# CP2102_USB_to_Serial_Breakout_v12.net
KiCad netlist of a schematic drawn in EAGLE
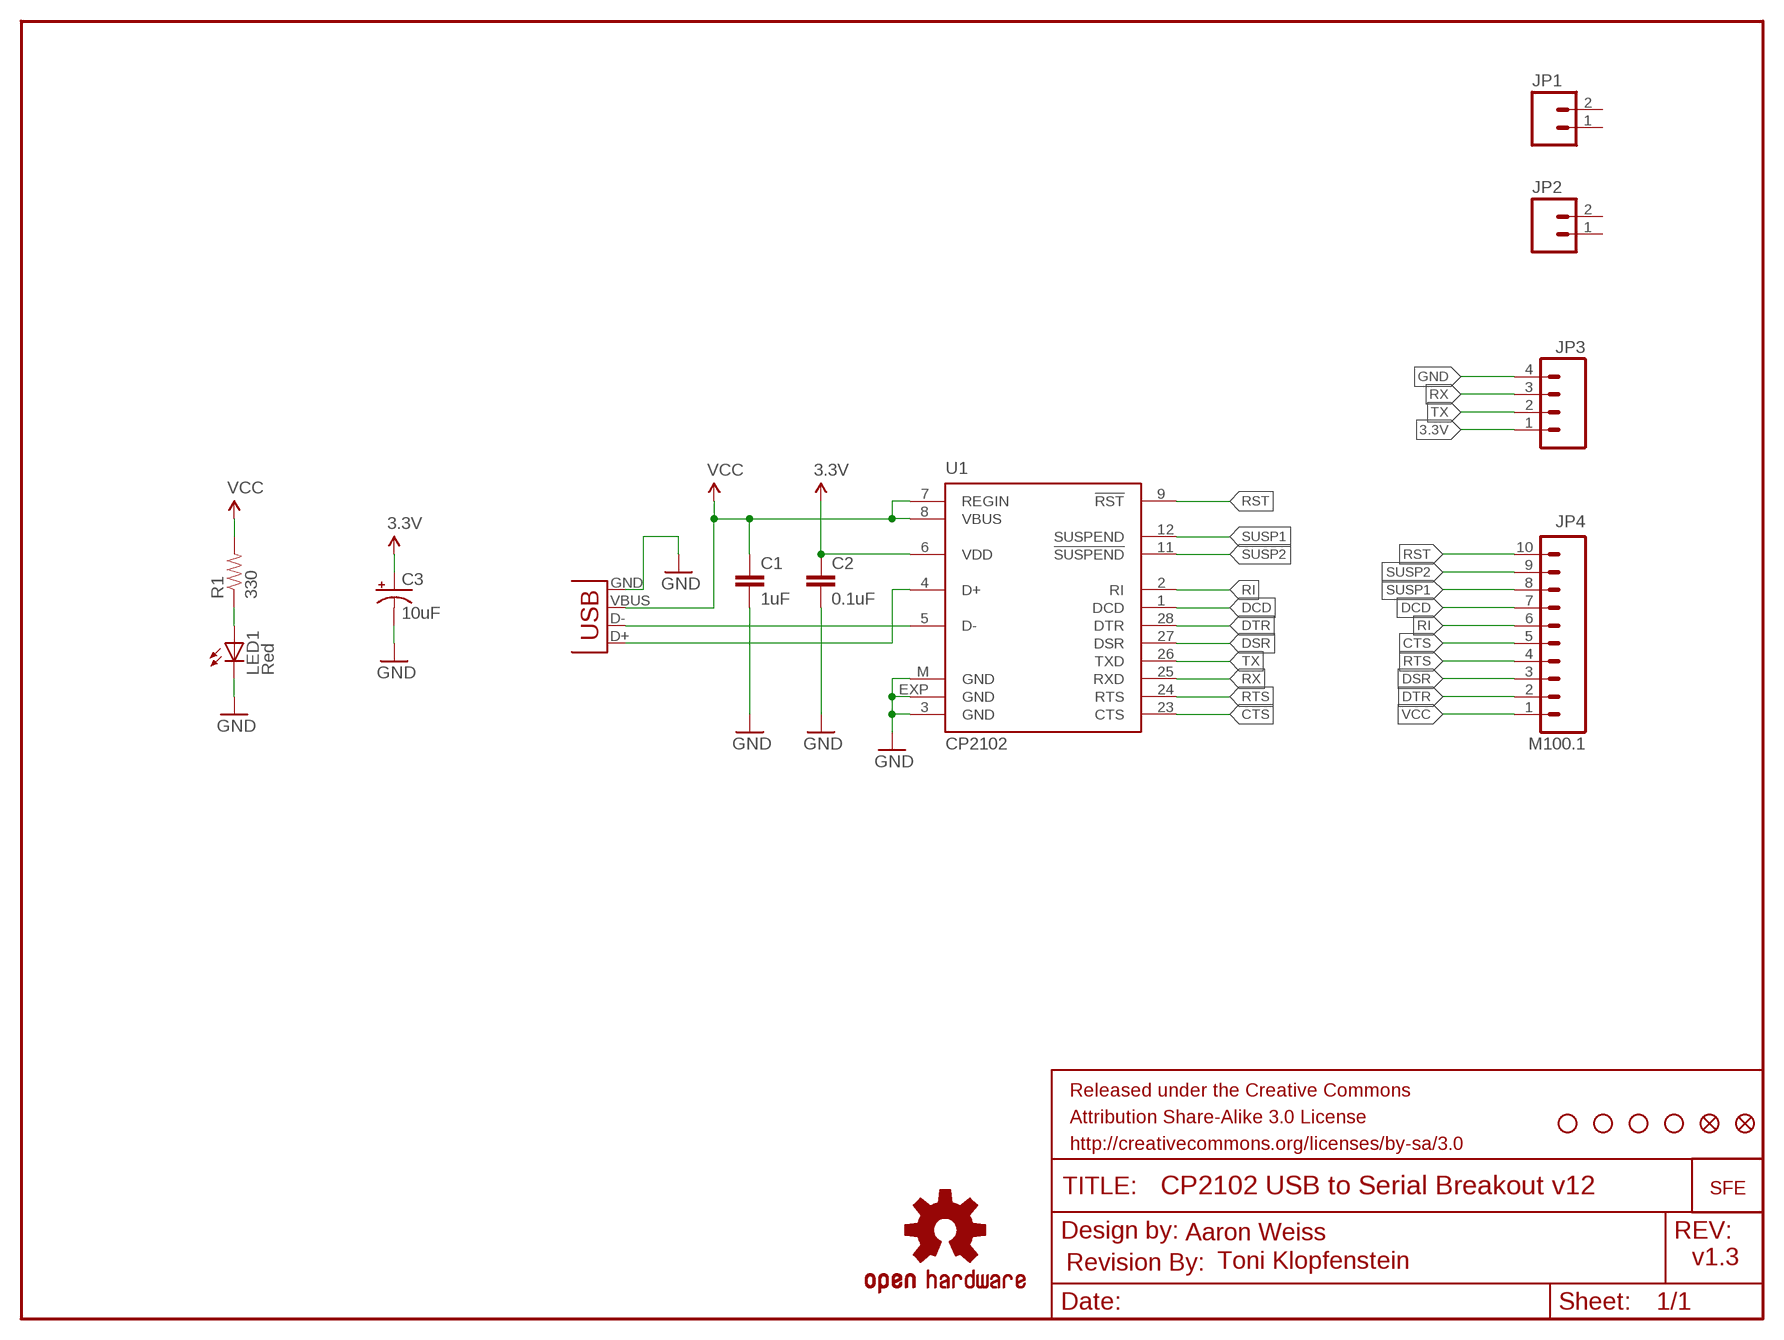
[diagram p0: schematic, sheet 1]

(export (version "E")
  (design (tool "Eeschema 10.0.6"))
  (components
    (comp (ref "C1")
      (value "1uF")
      (footprint "eagle-import:0603-CAP")
      (libsource (lib "eagle-import") (part "1.0UF-16V-10%(0603)"))
    )
    (comp (ref "C2")
      (value "0.1uF")
      (footprint "eagle-import:0603-CAP")
      (libsource (lib "eagle-import") (part "0.1UF-25V(+80/-20%)(0603)"))
    )
    (comp (ref "C3")
      (value "10uF")
      (footprint "eagle-import:EIA3216")
      (libsource (lib "eagle-import") (part "CAP_POL1206"))
    )
    (comp (ref "FRAME1")
      (value "FRAME-LETTER")
      (footprint "eagle-import:CREATIVE_COMMONS")
      (libsource (lib "eagle-import") (part "FRAME-LETTER"))
    )
    (comp (ref "JP1")
      (value "M02PTH")
      (footprint "eagle-import:1X02")
      (libsource (lib "eagle-import") (part "M02PTH"))
    )
    (comp (ref "JP2")
      (value "M02PTH")
      (footprint "eagle-import:1X02")
      (libsource (lib "eagle-import") (part "M02PTH"))
    )
    (comp (ref "JP3")
      (value "M04PTH")
      (footprint "eagle-import:1X04")
      (libsource (lib "eagle-import") (part "M04PTH"))
    )
    (comp (ref "JP4")
      (value "M100.1")
      (footprint "eagle-import:1X10")
      (libsource (lib "eagle-import") (part "M100.1"))
    )
    (comp (ref "LED1")
      (value "Red")
      (footprint "eagle-import:LED-1206")
      (libsource (lib "eagle-import") (part "LED1206"))
    )
    (comp (ref "LOGO1")
      (value "OSHW-LOGOS")
      (footprint "eagle-import:OSHW-LOGO-S")
      (libsource (lib "eagle-import") (part "OSHW-LOGOS"))
    )
    (comp (ref "R1")
      (value "330")
      (footprint "eagle-import:0603-RES")
      (libsource (lib "eagle-import") (part "330OHM1/10W1%(0603)"))
    )
    (comp (ref "U$1")
      (value "LOGO-SFENEW")
      (footprint "eagle-import:SFE-NEW-WEBLOGO")
      (libsource (lib "eagle-import") (part "LOGO-SFENEW"))
    )
    (comp (ref "U$2")
      (value "FIDUCIAL1X2")
      (footprint "eagle-import:FIDUCIAL-1X2")
      (libsource (lib "eagle-import") (part "FIDUCIAL1X2"))
    )
    (comp (ref "U$3")
      (value "FIDUCIAL1X2")
      (footprint "eagle-import:FIDUCIAL-1X2")
      (libsource (lib "eagle-import") (part "FIDUCIAL1X2"))
    )
    (comp (ref "U$4")
      (value "REVISION")
      (footprint "eagle-import:REVISION")
      (libsource (lib "eagle-import") (part "REVISION"))
    )
    (comp (ref "U$6")
      (value "STAND-OFF")
      (footprint "eagle-import:STAND-OFF")
      (libsource (lib "eagle-import") (part "STAND-OFF"))
    )
    (comp (ref "U$7")
      (value "STAND-OFF")
      (footprint "eagle-import:STAND-OFF")
      (libsource (lib "eagle-import") (part "STAND-OFF"))
    )
    (comp (ref "U$8")
      (value "STAND-OFF")
      (footprint "eagle-import:STAND-OFF")
      (libsource (lib "eagle-import") (part "STAND-OFF"))
    )
    (comp (ref "U$9")
      (value "STAND-OFF")
      (footprint "eagle-import:STAND-OFF")
      (libsource (lib "eagle-import") (part "STAND-OFF"))
    )
    (comp (ref "U1")
      (value "CP2102")
      (footprint "eagle-import:MLP28")
      (libsource (lib "eagle-import") (part "CP210X_USB_UART"))
    )
    (comp (ref "X1")
      (value "USBPTH")
      (footprint "eagle-import:USB-B-PTH")
      (libsource (lib "eagle-import") (part "USBPTH"))
    )
  )
  (nets
    (net (code "1") (name "3.3V") (class "Default")
      (node (ref "C2") (pin "1") (pinfunction "1_1") (pintype "passive"))
      (node (ref "C3") (pin "A") (pinfunction "+_A") (pintype "passive"))
      (node (ref "JP3") (pin "1") (pinfunction "1_1") (pintype "passive"))
      (node (ref "U1") (pin "6") (pinfunction "VDD_6") (pintype "power_in"))
    )
    (net (code "2") (name "CTS") (class "Default")
      (node (ref "JP4") (pin "5") (pinfunction "5_5") (pintype "passive"))
      (node (ref "U1") (pin "23") (pinfunction "CTS_23") (pintype "input"))
    )
    (net (code "3") (name "DCD") (class "Default")
      (node (ref "JP4") (pin "7") (pinfunction "7_7") (pintype "passive"))
      (node (ref "U1") (pin "1") (pinfunction "DCD_1") (pintype "input"))
    )
    (net (code "4") (name "DSR") (class "Default")
      (node (ref "JP4") (pin "3") (pinfunction "3_3") (pintype "passive"))
      (node (ref "U1") (pin "27") (pinfunction "DSR_27") (pintype "input"))
    )
    (net (code "5") (name "DTR") (class "Default")
      (node (ref "JP4") (pin "2") (pinfunction "2_2") (pintype "passive"))
      (node (ref "U1") (pin "28") (pinfunction "DTR_28") (pintype "output"))
    )
    (net (code "6") (name "GND") (class "Default")
      (node (ref "C1") (pin "2") (pinfunction "2_2") (pintype "passive"))
      (node (ref "C2") (pin "2") (pinfunction "2_2") (pintype "passive"))
      (node (ref "C3") (pin "C") (pinfunction "-_C") (pintype "passive"))
      (node (ref "JP3") (pin "4") (pinfunction "4_4") (pintype "passive"))
      (node (ref "LED1") (pin "C") (pinfunction "C_C") (pintype "passive"))
      (node (ref "U1") (pin "3") (pinfunction "GND_3") (pintype "power_in"))
      (node (ref "U1") (pin "EXP") (pinfunction "GND_EXP") (pintype "power_in"))
      (node (ref "U1") (pin "M") (pinfunction "GND_M") (pintype "power_in"))
      (node (ref "X1") (pin "GND") (pinfunction "GND_GND") (pintype "bidirectional"))
    )
    (net (code "7") (name "Net-(LED1-PadA)") (class "Default")
      (node (ref "LED1") (pin "A") (pinfunction "A_A") (pintype "passive"))
      (node (ref "R1") (pin "1") (pinfunction "1_1") (pintype "passive"))
    )
    (net (code "8") (name "Net-(U1-D+)") (class "Default")
      (node (ref "U1") (pin "4") (pinfunction "D+_4") (pintype "bidirectional"))
      (node (ref "X1") (pin "D+") (pinfunction "D+_D+") (pintype "bidirectional"))
    )
    (net (code "9") (name "Net-(U1-D-)") (class "Default")
      (node (ref "U1") (pin "5") (pinfunction "D-_5") (pintype "bidirectional"))
      (node (ref "X1") (pin "D-") (pinfunction "D-_D-") (pintype "bidirectional"))
    )
    (net (code "10") (name "RI") (class "Default")
      (node (ref "JP4") (pin "6") (pinfunction "6_6") (pintype "passive"))
      (node (ref "U1") (pin "2") (pinfunction "RI_2") (pintype "input"))
    )
    (net (code "11") (name "RST") (class "Default")
      (node (ref "JP4") (pin "10") (pinfunction "10_10") (pintype "passive"))
      (node (ref "U1") (pin "9") (pinfunction "~{RST}_9") (pintype "bidirectional"))
    )
    (net (code "12") (name "RTS") (class "Default")
      (node (ref "JP4") (pin "4") (pinfunction "4_4") (pintype "passive"))
      (node (ref "U1") (pin "24") (pinfunction "RTS_24") (pintype "output"))
    )
    (net (code "13") (name "RX") (class "Default")
      (node (ref "JP3") (pin "3") (pinfunction "3_3") (pintype "passive"))
      (node (ref "U1") (pin "25") (pinfunction "RXD_25") (pintype "input"))
    )
    (net (code "14") (name "SUSP1") (class "Default")
      (node (ref "JP4") (pin "8") (pinfunction "8_8") (pintype "passive"))
      (node (ref "U1") (pin "12") (pinfunction "SUSPEND_12") (pintype "output"))
    )
    (net (code "15") (name "SUSP2") (class "Default")
      (node (ref "JP4") (pin "9") (pinfunction "9_9") (pintype "passive"))
      (node (ref "U1") (pin "11") (pinfunction "~{SUSPEND}_11") (pintype "output"))
    )
    (net (code "16") (name "TX") (class "Default")
      (node (ref "JP3") (pin "2") (pinfunction "2_2") (pintype "passive"))
      (node (ref "U1") (pin "26") (pinfunction "TXD_26") (pintype "output"))
    )
    (net (code "17") (name "VCC") (class "Default")
      (node (ref "C1") (pin "1") (pinfunction "1_1") (pintype "passive"))
      (node (ref "JP4") (pin "1") (pinfunction "1_1") (pintype "passive"))
      (node (ref "R1") (pin "2") (pinfunction "2_2") (pintype "passive"))
      (node (ref "U1") (pin "7") (pinfunction "REGIN_7") (pintype "passive"))
      (node (ref "U1") (pin "8") (pinfunction "VBUS_8") (pintype "input"))
      (node (ref "X1") (pin "VBUS") (pinfunction "VBUS_VBUS") (pintype "bidirectional"))
    )
    (net (code "18") (name "unconnected-(JP1-Pad1)") (class "Default")
      (node (ref "JP1") (pin "1") (pinfunction "1_1") (pintype "passive"))
    )
    (net (code "19") (name "unconnected-(JP1-Pad2)") (class "Default")
      (node (ref "JP1") (pin "2") (pinfunction "2_2") (pintype "passive"))
    )
    (net (code "20") (name "unconnected-(JP2-Pad1)") (class "Default")
      (node (ref "JP2") (pin "1") (pinfunction "1_1") (pintype "passive"))
    )
    (net (code "21") (name "unconnected-(JP2-Pad2)") (class "Default")
      (node (ref "JP2") (pin "2") (pinfunction "2_2") (pintype "passive"))
    )
  )
)
